# ESP32_with_USBC.net
KiCad netlist of a schematic drawn in Altium Designer
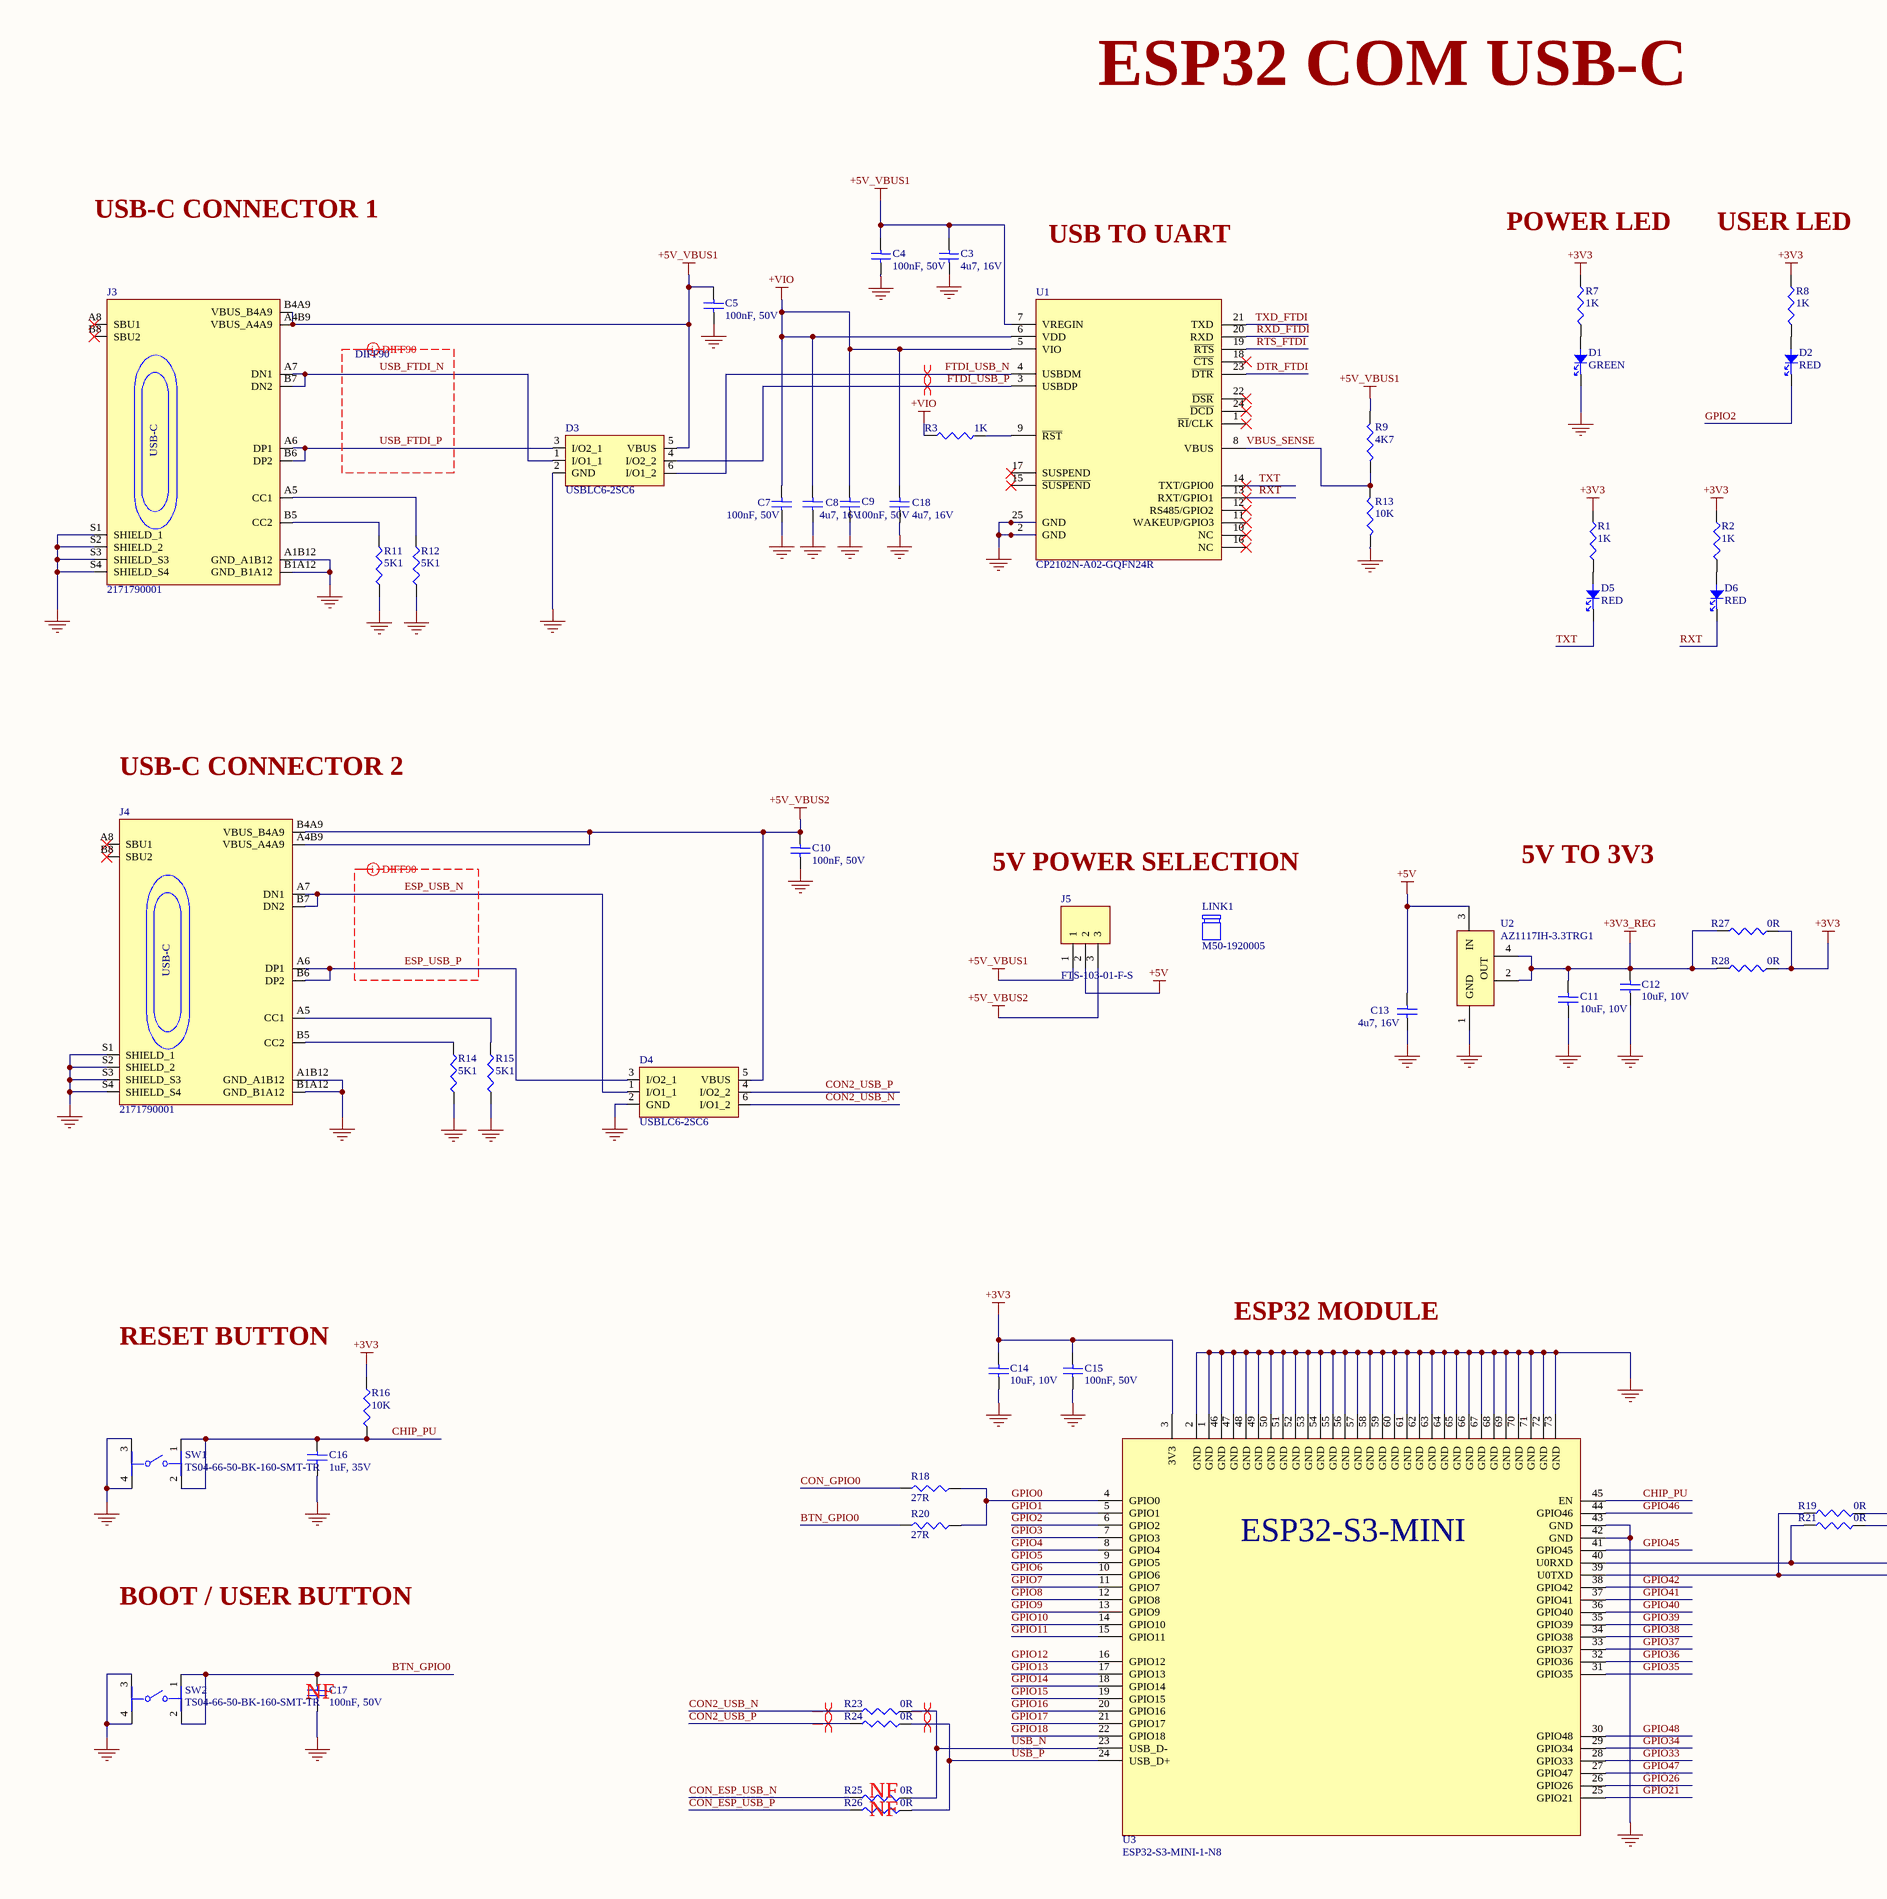
[diagram p0: ESP32 with USBC.SchDoc, left]
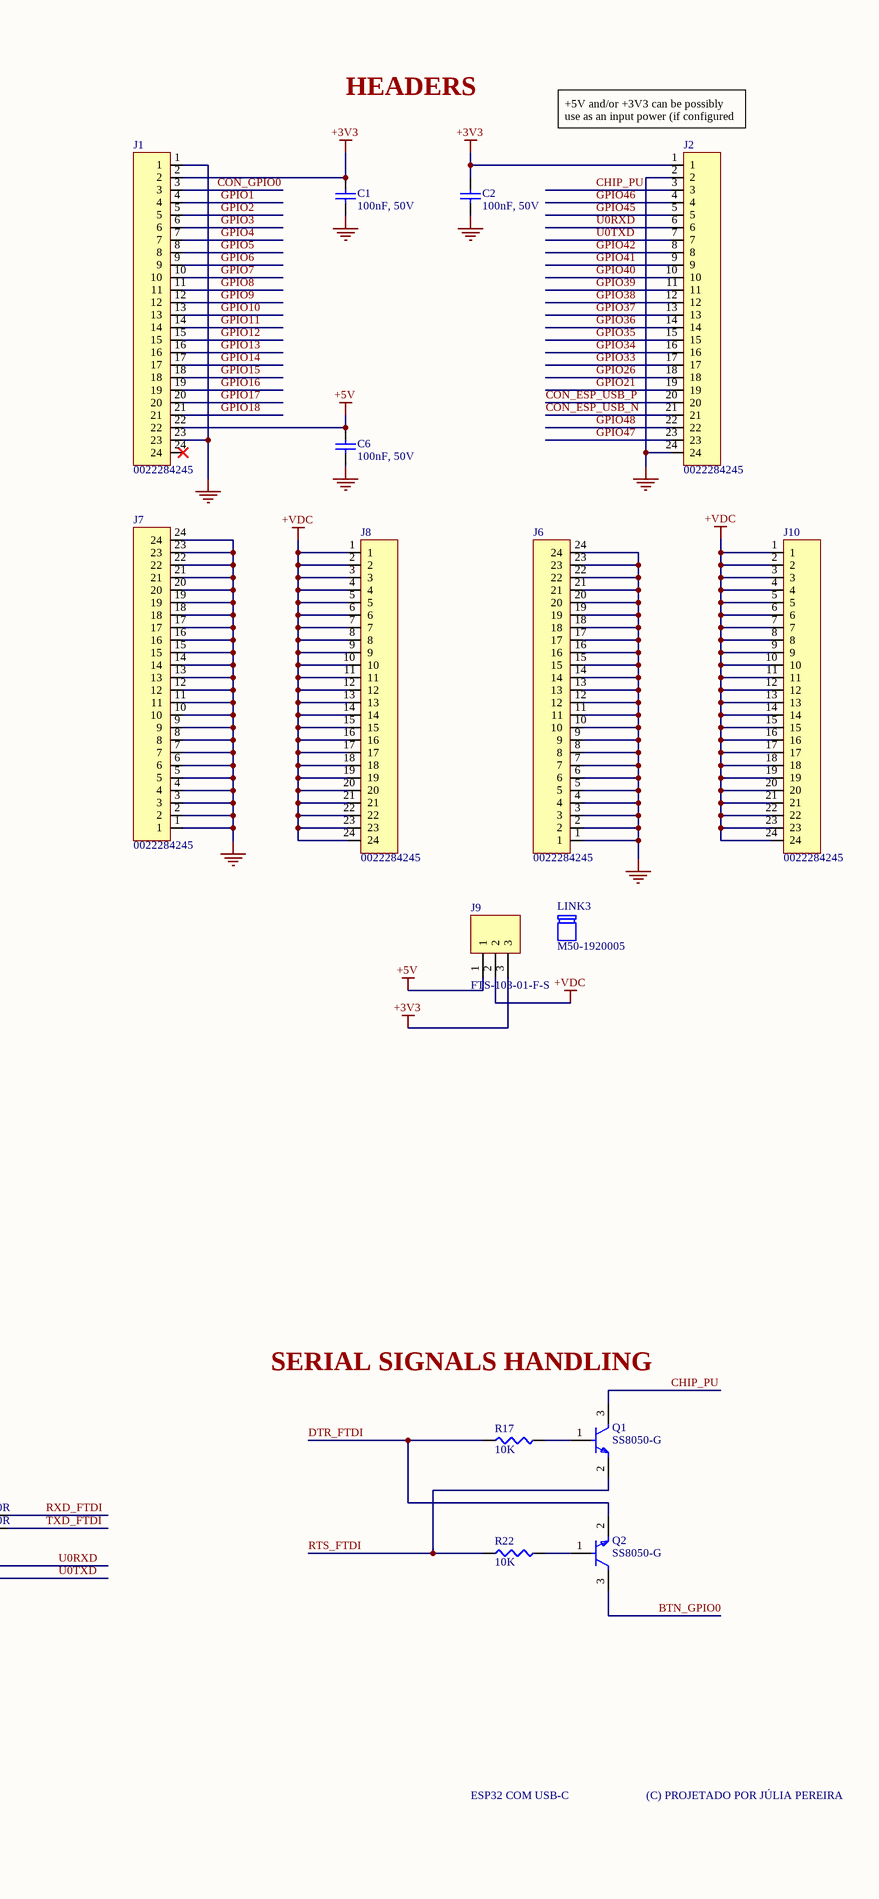
[diagram p1: ESP32 with USBC.SchDoc, right]

(export (version "E")
  (design (tool "Eeschema 10.0.6"))
  (components
    (comp (ref "C1")
      (value "100nF, 50V")
      (footprint "CAPC1005X65N")
      (description "CAP CER 0.1UF 50V X7R 0402")
      (fields
        (field (name "MANUFACTURER") "Samsung Electro-Mechanics")
        (field (name "MANUFACTURER PART NUMBER") "CL05B104KB54PNC")
      )
      (libsource (lib "Schlib") (part "CL05B104KB54PNC"))
    )
    (comp (ref "C2")
      (value "100nF, 50V")
      (footprint "CAPC1005X65N")
      (description "CAP CER 0.1UF 50V X7R 0402")
      (fields
        (field (name "MANUFACTURER") "Samsung Electro-Mechanics")
        (field (name "MANUFACTURER PART NUMBER") "CL05B104KB54PNC")
      )
      (libsource (lib "Schlib") (part "CL05B104KB54PNC"))
    )
    (comp (ref "C3")
      (value "4u7, 16V")
      (footprint "CAPC1005X65N")
      (description "4.7 µF ±20% 16V Capacitor de cerâmica X5R 0402 (métrico 1005)")
      (fields
        (field (name "MANUFACTURER") "Samsung Electro-Mechanics")
        (field (name "MANUFACTURER PART NUMBER") "CL05A475MO5NUNC")
      )
      (libsource (lib "Schlib") (part "CL05A475MO5NUNC"))
    )
    (comp (ref "C4")
      (value "100nF, 50V")
      (footprint "CAPC1005X65N")
      (description "CAP CER 0.1UF 50V X7R 0402")
      (fields
        (field (name "MANUFACTURER") "Samsung Electro-Mechanics")
        (field (name "MANUFACTURER PART NUMBER") "CL05B104KB54PNC")
      )
      (libsource (lib "Schlib") (part "CL05B104KB54PNC"))
    )
    (comp (ref "C5")
      (value "100nF, 50V")
      (footprint "CAPC1005X65N")
      (description "CAP CER 0.1UF 50V X7R 0402")
      (fields
        (field (name "MANUFACTURER") "Samsung Electro-Mechanics")
        (field (name "MANUFACTURER PART NUMBER") "CL05B104KB54PNC")
      )
      (libsource (lib "Schlib") (part "CL05B104KB54PNC"))
    )
    (comp (ref "C6")
      (value "100nF, 50V")
      (footprint "CAPC1005X65N")
      (description "CAP CER 0.1UF 50V X7R 0402")
      (fields
        (field (name "MANUFACTURER") "Samsung Electro-Mechanics")
        (field (name "MANUFACTURER PART NUMBER") "CL05B104KB54PNC")
      )
      (libsource (lib "Schlib") (part "CL05B104KB54PNC"))
    )
    (comp (ref "C7")
      (value "100nF, 50V")
      (footprint "CAPC1005X65N")
      (description "CAP CER 0.1UF 50V X7R 0402")
      (fields
        (field (name "MANUFACTURER") "Samsung Electro-Mechanics")
        (field (name "MANUFACTURER PART NUMBER") "CL05B104KB54PNC")
      )
      (libsource (lib "Schlib") (part "CL05B104KB54PNC"))
    )
    (comp (ref "C8")
      (value "4u7, 16V")
      (footprint "CAPC1005X65N")
      (description "4.7 µF ±20% 16V Capacitor de cerâmica X5R 0402 (métrico 1005)")
      (fields
        (field (name "MANUFACTURER") "Samsung Electro-Mechanics")
        (field (name "MANUFACTURER PART NUMBER") "CL05A475MO5NUNC")
      )
      (libsource (lib "Schlib") (part "CL05A475MO5NUNC"))
    )
    (comp (ref "C9")
      (value "100nF, 50V")
      (footprint "CAPC1005X65N")
      (description "CAP CER 0.1UF 50V X7R 0402")
      (fields
        (field (name "MANUFACTURER") "Samsung Electro-Mechanics")
        (field (name "MANUFACTURER PART NUMBER") "CL05B104KB54PNC")
      )
      (libsource (lib "Schlib") (part "CL05B104KB54PNC"))
    )
    (comp (ref "C10")
      (value "100nF, 50V")
      (footprint "CAPC1005X65N")
      (description "CAP CER 0.1UF 50V X7R 0402")
      (fields
        (field (name "MANUFACTURER") "Samsung Electro-Mechanics")
        (field (name "MANUFACTURER PART NUMBER") "CL05B104KB54PNC")
      )
      (libsource (lib "Schlib") (part "CL05B104KB54PNC"))
    )
    (comp (ref "C11")
      (value "10uF, 10V")
      (footprint "CAPC1005X65N")
      (description "10 µF ±20% 10V Capacitor de cerâmica X5R 0402 (métrico 1005)")
      (fields
        (field (name "MANUFACTURER") "Samsung Electro-Mechanics")
        (field (name "MANUFACTURER PART NUMBER") "CL05A106MP8NUB8")
      )
      (libsource (lib "Schlib") (part "CL05A106MP8NUB8"))
    )
    (comp (ref "C12")
      (value "10uF, 10V")
      (footprint "CAPC1005X65N")
      (description "10 µF ±20% 10V Capacitor de cerâmica X5R 0402 (métrico 1005)")
      (fields
        (field (name "MANUFACTURER") "Samsung Electro-Mechanics")
        (field (name "MANUFACTURER PART NUMBER") "CL05A106MP8NUB8")
      )
      (libsource (lib "Schlib") (part "CL05A106MP8NUB8"))
    )
    (comp (ref "C13")
      (value "4u7, 16V")
      (footprint "CAPC1005X65N")
      (description "4.7 µF ±20% 16V Capacitor de cerâmica X5R 0402 (métrico 1005)")
      (fields
        (field (name "MANUFACTURER") "Samsung Electro-Mechanics")
        (field (name "MANUFACTURER PART NUMBER") "CL05A475MO5NUNC")
      )
      (libsource (lib "Schlib") (part "CL05A475MO5NUNC"))
    )
    (comp (ref "C14")
      (value "10uF, 10V")
      (footprint "CAPC1005X65N")
      (description "10 µF ±20% 10V Capacitor de cerâmica X5R 0402 (métrico 1005)")
      (fields
        (field (name "MANUFACTURER") "Samsung Electro-Mechanics")
        (field (name "MANUFACTURER PART NUMBER") "CL05A106MP8NUB8")
      )
      (libsource (lib "Schlib") (part "CL05A106MP8NUB8"))
    )
    (comp (ref "C15")
      (value "100nF, 50V")
      (footprint "CAPC1005X65N")
      (description "CAP CER 0.1UF 50V X7R 0402")
      (fields
        (field (name "MANUFACTURER") "Samsung Electro-Mechanics")
        (field (name "MANUFACTURER PART NUMBER") "CL05B104KB54PNC")
      )
      (libsource (lib "Schlib") (part "CL05B104KB54PNC"))
    )
    (comp (ref "C16")
      (value "1uF, 35V")
      (footprint "CAPC1005X65N")
      (description "1 µF ±10% 35V Capacitor de cerâmica X5R 0402 (métrico 1005)")
      (fields
        (field (name "MANUFACTURER") "Samsung Electro-Mechanics")
        (field (name "MANUFACTURER PART NUMBER") "CL05A105KL5NRNC")
      )
      (libsource (lib "Schlib") (part "CL05A105KL5NRNC"))
    )
    (comp (ref "C17")
      (value "100nF, 50V")
      (footprint "CAPC1005X65N")
      (description "CAP CER 0.1UF 50V X7R 0402")
      (fields
        (field (name "MANUFACTURER") "Samsung Electro-Mechanics")
        (field (name "MANUFACTURER PART NUMBER") "CL05B104KB54PNC")
      )
      (libsource (lib "Schlib") (part "CL05B104KB54PNC"))
    )
    (comp (ref "C18")
      (value "4u7, 16V")
      (footprint "CAPC1005X65N")
      (description "4.7 µF ±20% 16V Capacitor de cerâmica X5R 0402 (métrico 1005)")
      (fields
        (field (name "MANUFACTURER") "Samsung Electro-Mechanics")
        (field (name "MANUFACTURER PART NUMBER") "CL05A475MO5NUNC")
      )
      (libsource (lib "Schlib") (part "CL05A475MO5NUNC"))
    )
    (comp (ref "D1")
      (value "GREEN")
      (footprint "LED0402G")
      (description "Verde 528nm Indicadores LED - Discreto 2,8V 0402 (métrico 1005)")
      (fields
        (field (name "MANUFACTURER") "Vishay")
        (field (name "MANUFACTURER PART NUMBER") "VLMTG1500-GS08")
      )
      (libsource (lib "Schlib") (part "VLMTG1500-GS08"))
    )
    (comp (ref "D2")
      (value "RED")
      (footprint "LED0402R")
      (description "LED Uni-Color Super Red 639nm 2-Pin Chip 0402(1006Metric) T/R")
      (fields
        (field (name "MANUFACTURER") "Vishay")
        (field (name "MANUFACTURER PART NUMBER") "VLMS1500-GS08")
      )
      (libsource (lib "Schlib") (part "VLMS1500-GS08"))
    )
    (comp (ref "D3")
      (value "USBLC6-2SC6")
      (footprint "SOT23-6L_STM-L")
      (description "STMicroelectronics Uni-Directional TVS Diode Array, 17V Vcl Max, SMD, SOT-23, 6V Vbr Min")
      (fields (field (name "MANUFACTURER") "STMicroelectronics"))
      (libsource (lib "Schlib") (part "USBLC6-2SC6"))
    )
    (comp (ref "D4")
      (value "USBLC6-2SC6")
      (footprint "SOT23-6L_STM-L")
      (description "STMicroelectronics Uni-Directional TVS Diode Array, 17V Vcl Max, SMD, SOT-23, 6V Vbr Min")
      (fields (field (name "MANUFACTURER") "STMicroelectronics"))
      (libsource (lib "Schlib") (part "USBLC6-2SC6"))
    )
    (comp (ref "D5")
      (value "RED")
      (footprint "LED0402R")
      (description "LED Uni-Color Super Red 639nm 2-Pin Chip 0402(1006Metric) T/R")
      (fields
        (field (name "MANUFACTURER") "Vishay")
        (field (name "MANUFACTURER PART NUMBER") "VLMS1500-GS08")
      )
      (libsource (lib "Schlib") (part "VLMS1500-GS08"))
    )
    (comp (ref "D6")
      (value "RED")
      (footprint "LED0402R")
      (description "LED Uni-Color Super Red 639nm 2-Pin Chip 0402(1006Metric) T/R")
      (fields
        (field (name "MANUFACTURER") "Vishay")
        (field (name "MANUFACTURER PART NUMBER") "VLMS1500-GS08")
      )
      (libsource (lib "Schlib") (part "VLMS1500-GS08"))
    )
    (comp (ref "J1")
      (value "0022284245")
      (footprint "HDR_1X24_2.54MM")
      (description "Conector barra de pinos Furo passante 24 position 0,100\" (2,54mm)")
      (fields (field (name "MANUFACTURER") "Molex") (field (name "MANUFACTURER PART NUMBER") "22-28-4245"))
      (libsource (lib "") (part "0022284245_2"))
    )
    (comp (ref "J2")
      (value "0022284245")
      (footprint "HDR_1X24_2.54MM")
      (description "Conector barra de pinos Furo passante 24 position 0,100\" (2,54mm)")
      (fields (field (name "MANUFACTURER") "Molex") (field (name "MANUFACTURER PART NUMBER") "22-28-4245"))
      (libsource (lib "") (part "0022284245_1"))
    )
    (comp (ref "J3")
      (value "2171790001")
      (footprint "FP-2171790001-MFG")
      (fields (field (name "MANUFACTURER") "Molex") (field (name "MANUFACTURER PART NUMBER") "217179-0001"))
      (libsource (lib "Schlib") (part "217179-0001"))
    )
    (comp (ref "J4")
      (value "2171790001")
      (footprint "FP-2171790001-MFG")
      (fields (field (name "MANUFACTURER") "Molex") (field (name "MANUFACTURER PART NUMBER") "217179-0001"))
      (libsource (lib "Schlib") (part "217179-0001"))
    )
    (comp (ref "J5")
      (value "FTS-103-01-F-S")
      (footprint "HDR_1X3_2X54MM")
      (description "Conector barra de pinos Furo passante 3 position 0,050\" (1,27mm)")
      (fields (field (name "MANUFACTURER") "Samtec"))
      (libsource (lib "Schlib") (part "FTS-103-01-F-S"))
    )
    (comp (ref "J6")
      (value "0022284245")
      (footprint "HDR_1X24_2.54MM")
      (description "Conector barra de pinos Furo passante 24 position 0,100\" (2,54mm)")
      (fields (field (name "MANUFACTURER") "Molex") (field (name "MANUFACTURER PART NUMBER") "22-28-4245"))
      (libsource (lib "Schlib") (part "0022284245"))
    )
    (comp (ref "J7")
      (value "0022284245")
      (footprint "HDR_1X24_2.54MM")
      (description "Conector barra de pinos Furo passante 24 position 0,100\" (2,54mm)")
      (fields (field (name "MANUFACTURER") "Molex") (field (name "MANUFACTURER PART NUMBER") "22-28-4245"))
      (libsource (lib "Schlib") (part "0022284245"))
    )
    (comp (ref "J8")
      (value "0022284245")
      (footprint "HDR_1X24_2.54MM")
      (description "Conector barra de pinos Furo passante 24 position 0,100\" (2,54mm)")
      (fields (field (name "MANUFACTURER") "Molex") (field (name "MANUFACTURER PART NUMBER") "22-28-4245"))
      (libsource (lib "") (part "0022284245_1"))
    )
    (comp (ref "J9")
      (value "FTS-103-01-F-S")
      (footprint "HDR_1X3_2X54MM")
      (description "Conector barra de pinos Furo passante 3 position 0,050\" (1,27mm)")
      (fields (field (name "MANUFACTURER") "Samtec"))
      (libsource (lib "Schlib") (part "FTS-103-01-F-S"))
    )
    (comp (ref "J10")
      (value "0022284245")
      (footprint "HDR_1X24_2.54MM")
      (description "Conector barra de pinos Furo passante 24 position 0,100\" (2,54mm)")
      (fields (field (name "MANUFACTURER") "Molex") (field (name "MANUFACTURER PART NUMBER") "22-28-4245"))
      (libsource (lib "") (part "0022284245_1"))
    )
    (comp (ref "LINK1")
      (value "M50-1920005")
      (description "2 (1 x 2) Conector Shunt com posi玢o Vermelho Topo fechado 0,050\" (1,27mm) Ouro")
      (fields (field (name "MANUFACTURER") "Harwin"))
      (libsource (lib "Schlib") (part "M50-1920005"))
    )
    (comp (ref "LINK3")
      (value "M50-1920005")
      (description "2 (1 x 2) Conector Shunt com posi玢o Vermelho Topo fechado 0,050\" (1,27mm) Ouro")
      (fields (field (name "MANUFACTURER") "Harwin"))
      (libsource (lib "Schlib") (part "M50-1920005"))
    )
    (comp (ref "Q1")
      (value "SS8050-G")
      (footprint "FP-SS8050-G-IPC_B")
      (description "Transístor bipolar (BJT) NPN 25 V 1.5 A 100MHz 300 mW Montagem em superfície SOT-23-3")
      (fields (field (name "MANUFACTURER") "Comchip"))
      (libsource (lib "Schlib") (part "SS8050-G"))
    )
    (comp (ref "Q2")
      (value "SS8050-G")
      (footprint "FP-SS8050-G-IPC_B")
      (description "Transístor bipolar (BJT) NPN 25 V 1.5 A 100MHz 300 mW Montagem em superfície SOT-23-3")
      (fields (field (name "MANUFACTURER") "Comchip"))
      (libsource (lib "Schlib") (part "SS8050-G"))
    )
    (comp (ref "R1")
      (value "1K")
      (footprint "RESC1005X37N")
      (description "1 kOhms ±1% 0,063W, 1/16W Resistor de chip 0402 (métrico 1005) Resistente à umidade Filme grosso")
      (fields
        (field (name "MANUFACTURER") "Yageo Group")
        (field (name "MANUFACTURER PART NUMBER") "RC0402FR-071KL")
      )
      (libsource (lib "Schlib") (part "RC0402FR-071KL"))
    )
    (comp (ref "R2")
      (value "1K")
      (footprint "RESC1005X37N")
      (description "1 kOhms ±1% 0,063W, 1/16W Resistor de chip 0402 (métrico 1005) Resistente à umidade Filme grosso")
      (fields
        (field (name "MANUFACTURER") "Yageo Group")
        (field (name "MANUFACTURER PART NUMBER") "RC0402FR-071KL")
      )
      (libsource (lib "Schlib") (part "RC0402FR-071KL"))
    )
    (comp (ref "R3")
      (value "1K")
      (footprint "RESC1005X37N")
      (description "1 kOhms ±1% 0,063W, 1/16W Resistor de chip 0402 (métrico 1005) Resistente à umidade Filme grosso")
      (fields
        (field (name "MANUFACTURER") "Yageo Group")
        (field (name "MANUFACTURER PART NUMBER") "RC0402FR-071KL")
      )
      (libsource (lib "Schlib") (part "RC0402FR-071KL"))
    )
    (comp (ref "R7")
      (value "1K")
      (footprint "RESC1005X37N")
      (description "1 kOhms ±1% 0,063W, 1/16W Resistor de chip 0402 (métrico 1005) Resistente à umidade Filme grosso")
      (fields
        (field (name "MANUFACTURER") "Yageo Group")
        (field (name "MANUFACTURER PART NUMBER") "RC0402FR-071KL")
      )
      (libsource (lib "Schlib") (part "RC0402FR-071KL"))
    )
    (comp (ref "R8")
      (value "1K")
      (footprint "RESC1005X37N")
      (description "1 kOhms ±1% 0,063W, 1/16W Resistor de chip 0402 (métrico 1005) Resistente à umidade Filme grosso")
      (fields
        (field (name "MANUFACTURER") "Yageo Group")
        (field (name "MANUFACTURER PART NUMBER") "RC0402FR-071KL")
      )
      (libsource (lib "Schlib") (part "RC0402FR-071KL"))
    )
    (comp (ref "R9")
      (value "4K7")
      (footprint "RESC1005X37N")
      (description "RES 4.7K OHM 1% 1/16W 0402")
      (fields
        (field (name "MANUFACTURER") "Yageo Group")
        (field (name "MANUFACTURER PART NUMBER") "RC0402FR-074K7L")
      )
      (libsource (lib "Schlib") (part "RC0402FR-074K7L"))
    )
    (comp (ref "R11")
      (value "5K1")
      (footprint "RESC1005X37N")
      (fields
        (field (name "MANUFACTURER") "Yageo Group")
        (field (name "MANUFACTURER PART NUMBER") "AC0402FR-075K1L")
        (field (name "TOLERANCE") "1%")
      )
      (libsource (lib "Schlib") (part "AC0402FR-075K1L"))
    )
    (comp (ref "R12")
      (value "5K1")
      (footprint "RESC1005X37N")
      (fields
        (field (name "MANUFACTURER") "Yageo Group")
        (field (name "MANUFACTURER PART NUMBER") "AC0402FR-075K1L")
        (field (name "TOLERANCE") "1%")
      )
      (libsource (lib "Schlib") (part "AC0402FR-075K1L"))
    )
    (comp (ref "R13")
      (value "10K")
      (footprint "RESC1005X37N")
      (fields
        (field (name "MANUFACTURER") "Yageo Group")
        (field (name "MANUFACTURER PART NUMBER") "AC0402FR-0710KL")
        (field (name "TOLERANCE") "1%")
      )
      (libsource (lib "Schlib") (part "AC0402FR-0710KL"))
    )
    (comp (ref "R14")
      (value "5K1")
      (footprint "RESC1005X37N")
      (fields
        (field (name "MANUFACTURER") "Yageo Group")
        (field (name "MANUFACTURER PART NUMBER") "AC0402FR-075K1L")
        (field (name "TOLERANCE") "1%")
      )
      (libsource (lib "Schlib") (part "AC0402FR-075K1L"))
    )
    (comp (ref "R15")
      (value "5K1")
      (footprint "RESC1005X37N")
      (fields
        (field (name "MANUFACTURER") "Yageo Group")
        (field (name "MANUFACTURER PART NUMBER") "AC0402FR-075K1L")
        (field (name "TOLERANCE") "1%")
      )
      (libsource (lib "Schlib") (part "AC0402FR-075K1L"))
    )
    (comp (ref "R16")
      (value "10K")
      (footprint "RESC1005X37N")
      (fields
        (field (name "MANUFACTURER") "Yageo Group")
        (field (name "MANUFACTURER PART NUMBER") "AC0402FR-0710KL")
        (field (name "TOLERANCE") "1%")
      )
      (libsource (lib "Schlib") (part "AC0402FR-0710KL"))
    )
    (comp (ref "R17")
      (value "10K")
      (footprint "RESC1005X37N")
      (fields
        (field (name "MANUFACTURER") "Yageo Group")
        (field (name "MANUFACTURER PART NUMBER") "AC0402FR-0710KL")
        (field (name "TOLERANCE") "1%")
      )
      (libsource (lib "Schlib") (part "AC0402FR-0710KL"))
    )
    (comp (ref "R18")
      (value "27R")
      (footprint "RESC1005X37N")
      (description "27 Ohms ±1% 0,063W, 1/16W Resistor de chip 0402 (métrico 1005) Resistente à umidade Filme grosso")
      (fields
        (field (name "MANUFACTURER") "Yageo Group")
        (field (name "MANUFACTURER PART NUMBER") "RC0402FR-0727RL")
      )
      (libsource (lib "Schlib") (part "RC0402FR-0727RL"))
    )
    (comp (ref "R19")
      (value "0R")
      (footprint "RESC1005X37N")
      (description "0 Ohms Jumper Resistor de chip 0402 (métrico 1005) Resistente à umidade Filme grosso")
      (fields
        (field (name "MANUFACTURER") "Yageo Group")
        (field (name "MANUFACTURER PART NUMBER") "RC0402JR-070RL")
      )
      (libsource (lib "Schlib") (part "RC0402JR-070RL"))
    )
    (comp (ref "R20")
      (value "27R")
      (footprint "RESC1005X37N")
      (description "27 Ohms ±1% 0,063W, 1/16W Resistor de chip 0402 (métrico 1005) Resistente à umidade Filme grosso")
      (fields
        (field (name "MANUFACTURER") "Yageo Group")
        (field (name "MANUFACTURER PART NUMBER") "RC0402FR-0727RL")
      )
      (libsource (lib "Schlib") (part "RC0402FR-0727RL"))
    )
    (comp (ref "R21")
      (value "0R")
      (footprint "RESC1005X37N")
      (description "0 Ohms Jumper Resistor de chip 0402 (métrico 1005) Resistente à umidade Filme grosso")
      (fields
        (field (name "MANUFACTURER") "Yageo Group")
        (field (name "MANUFACTURER PART NUMBER") "RC0402JR-070RL")
      )
      (libsource (lib "Schlib") (part "RC0402JR-070RL"))
    )
    (comp (ref "R22")
      (value "10K")
      (footprint "RESC1005X37N")
      (fields
        (field (name "MANUFACTURER") "Yageo Group")
        (field (name "MANUFACTURER PART NUMBER") "AC0402FR-0710KL")
        (field (name "TOLERANCE") "1%")
      )
      (libsource (lib "Schlib") (part "AC0402FR-0710KL"))
    )
    (comp (ref "R23")
      (value "0R")
      (footprint "RESC1005X37N")
      (description "0 Ohms Jumper Resistor de chip 0402 (métrico 1005) Resistente à umidade Filme grosso")
      (fields
        (field (name "MANUFACTURER") "Yageo Group")
        (field (name "MANUFACTURER PART NUMBER") "RC0402JR-070RL")
      )
      (libsource (lib "Schlib") (part "RC0402JR-070RL"))
    )
    (comp (ref "R24")
      (value "0R")
      (footprint "RESC1005X37N")
      (description "0 Ohms Jumper Resistor de chip 0402 (métrico 1005) Resistente à umidade Filme grosso")
      (fields
        (field (name "MANUFACTURER") "Yageo Group")
        (field (name "MANUFACTURER PART NUMBER") "RC0402JR-070RL")
      )
      (libsource (lib "Schlib") (part "RC0402JR-070RL"))
    )
    (comp (ref "R25")
      (value "0R")
      (footprint "RESC1005X37N")
      (description "0 Ohms Jumper Resistor de chip 0402 (métrico 1005) Resistente à umidade Filme grosso")
      (fields
        (field (name "MANUFACTURER") "Yageo Group")
        (field (name "MANUFACTURER PART NUMBER") "RC0402JR-070RL")
      )
      (libsource (lib "Schlib") (part "RC0402JR-070RL"))
    )
    (comp (ref "R26")
      (value "0R")
      (footprint "RESC1005X37N")
      (description "0 Ohms Jumper Resistor de chip 0402 (métrico 1005) Resistente à umidade Filme grosso")
      (fields
        (field (name "MANUFACTURER") "Yageo Group")
        (field (name "MANUFACTURER PART NUMBER") "RC0402JR-070RL")
      )
      (libsource (lib "Schlib") (part "RC0402JR-070RL"))
    )
    (comp (ref "R27")
      (value "0R")
      (footprint "RESC2012X60N")
      (description "RESA-AS 0805 0R JUMPER 125MW")
      (fields
        (field (name "MANUFACTURER") "Bourns")
        (field (name "MANUFACTURER PART NUMBER") "CR0805AJ/-000EAS")
      )
      (libsource (lib "Schlib") (part "CR0805AJ/-000EAS"))
    )
    (comp (ref "R28")
      (value "0R")
      (footprint "RESC2012X60N")
      (description "RESA-AS 0805 0R JUMPER 125MW")
      (fields
        (field (name "MANUFACTURER") "Bourns")
        (field (name "MANUFACTURER PART NUMBER") "CR0805AJ/-000EAS")
      )
      (libsource (lib "Schlib") (part "CR0805AJ/-000EAS"))
    )
    (comp (ref "SW1")
      (value "TS04-66-50-BK-160-SMT-TR")
      (footprint "TS04-66-50-BK-160-SMT-TR")
      (description "6 x 6 mm, 5 mm Actuator Height Off PCB, 160 gf, Black, Surface Mount, SPST, Tactile Switch")
      (fields (field (name "MANUFACTURER") "Same Sky"))
      (libsource (lib "Schlib") (part "TS04-66-50-BK-160-SMT-TR"))
    )
    (comp (ref "SW2")
      (value "TS04-66-50-BK-160-SMT-TR")
      (footprint "TS04-66-50-BK-160-SMT-TR")
      (description "6 x 6 mm, 5 mm Actuator Height Off PCB, 160 gf, Black, Surface Mount, SPST, Tactile Switch")
      (fields (field (name "MANUFACTURER") "Same Sky"))
      (libsource (lib "Schlib") (part "TS04-66-50-BK-160-SMT-TR"))
    )
    (comp (ref "U1")
      (value "CP2102N-A02-GQFN24R")
      (footprint "QFN50P400X400X80-25N")
      (description "IC Usb to Uart Bridge QFN24 / Usb Bridge, Usb to Uart Usb 2.0 Uart Interface 24-QFN (4X4)")
      (fields (field (name "MANUFACTURER") "Silicon Lab"))
      (libsource (lib "Schlib") (part "CP2102N-A02-GQFN24R"))
    )
    (comp (ref "U2")
      (value "AZ1117IH-3.3TRG1")
      (footprint "DCY0004A_N")
      (description "LDO Voltage Regulator, 1 Output, Fixed, 0-15V in, 3.3V Out, 1.2V Drop, 1A out, SOT-223-3")
      (fields (field (name "MANUFACTURER") "Diodes Inc."))
      (libsource (lib "Schlib") (part "AZ1117IH-3.3TRG1"))
    )
    (comp (ref "U3")
      (value "ESP32-S3-MINI-1-N8")
      (footprint "XCVR_ESP32-S3-MINI-1-N8")
      (description "20.5dBm ESP32-S3FN8 Chip 2.4GHz SMD WiFi Modules ROHS")
      (fields (field (name "MANUFACTURER") "Espressif Systems"))
      (libsource (lib "Schlib") (part "ESP32-S3-MINI-1-N8"))
    )
  )
  (nets
    (net (code "1") (name "+3V3") (class "Default")
      (node (ref "C1") (pin "2") (pinfunction "2_2") (pintype "passive"))
      (node (ref "C14") (pin "2") (pinfunction "2_2") (pintype "passive"))
      (node (ref "C15") (pin "2") (pinfunction "2_2") (pintype "passive"))
      (node (ref "C2") (pin "2") (pinfunction "2_2") (pintype "passive"))
      (node (ref "J1") (pin "2") (pinfunction "2_2") (pintype "passive"))
      (node (ref "J2") (pin "1") (pinfunction "1_1") (pintype "passive"))
      (node (ref "J9") (pin "3") (pinfunction "3_3") (pintype "passive"))
      (node (ref "R1") (pin "2") (pinfunction "2_2") (pintype "passive"))
      (node (ref "R16") (pin "2") (pinfunction "2_2") (pintype "passive"))
      (node (ref "R2") (pin "2") (pinfunction "2_2") (pintype "passive"))
      (node (ref "R27") (pin "2") (pinfunction "2_2") (pintype "passive"))
      (node (ref "R28") (pin "2") (pinfunction "2_2") (pintype "passive"))
      (node (ref "R7") (pin "2") (pinfunction "2_2") (pintype "passive"))
      (node (ref "R8") (pin "2") (pinfunction "2_2") (pintype "passive"))
      (node (ref "U3") (pin "3") (pinfunction "3V3_3") (pintype "passive"))
    )
    (net (code "2") (name "+3V3_REG") (class "Default")
      (node (ref "C11") (pin "2") (pinfunction "2_2") (pintype "passive"))
      (node (ref "C12") (pin "2") (pinfunction "2_2") (pintype "passive"))
      (node (ref "R27") (pin "1") (pinfunction "1_1") (pintype "passive"))
      (node (ref "R28") (pin "1") (pinfunction "1_1") (pintype "passive"))
      (node (ref "U2") (pin "2") (pinfunction "OUT_2") (pintype "power_in"))
      (node (ref "U2") (pin "4") (pinfunction "OUT_4") (pintype "power_in"))
    )
    (net (code "3") (name "+5V") (class "Default")
      (node (ref "C13") (pin "2") (pinfunction "2_2") (pintype "passive"))
      (node (ref "C6") (pin "2") (pinfunction "2_2") (pintype "passive"))
      (node (ref "J1") (pin "22") (pinfunction "22_22") (pintype "passive"))
      (node (ref "J5") (pin "2") (pinfunction "2_2") (pintype "passive"))
      (node (ref "J9") (pin "1") (pinfunction "1_1") (pintype "passive"))
      (node (ref "U2") (pin "3") (pinfunction "IN_3") (pintype "power_in"))
    )
    (net (code "4") (name "+5V_VBUS1") (class "Default")
      (node (ref "C3") (pin "2") (pinfunction "2_2") (pintype "passive"))
      (node (ref "C4") (pin "2") (pinfunction "2_2") (pintype "passive"))
      (node (ref "C5") (pin "2") (pinfunction "2_2") (pintype "passive"))
      (node (ref "D3") (pin "5") (pinfunction "VBUS_5") (pintype "passive"))
      (node (ref "J3") (pin "A4B9") (pinfunction "VBUS_A4A9_A4B9") (pintype "passive"))
      (node (ref "J3") (pin "B4A9") (pinfunction "VBUS_B4A9_B4A9") (pintype "passive"))
      (node (ref "J5") (pin "1") (pinfunction "1_1") (pintype "passive"))
      (node (ref "R9") (pin "2") (pinfunction "2_2") (pintype "passive"))
      (node (ref "U1") (pin "7") (pinfunction "VREGIN_7") (pintype "passive"))
    )
    (net (code "5") (name "+5V_VBUS2") (class "Default")
      (node (ref "C10") (pin "2") (pinfunction "2_2") (pintype "passive"))
      (node (ref "D4") (pin "5") (pinfunction "VBUS_5") (pintype "passive"))
      (node (ref "J4") (pin "A4B9") (pinfunction "VBUS_A4A9_A4B9") (pintype "passive"))
      (node (ref "J4") (pin "B4A9") (pinfunction "VBUS_B4A9_B4A9") (pintype "passive"))
      (node (ref "J5") (pin "3") (pinfunction "3_3") (pintype "passive"))
    )
    (net (code "6") (name "+VDC") (class "Default")
      (node (ref "J10") (pin "1") (pinfunction "1_1") (pintype "passive"))
      (node (ref "J10") (pin "10") (pinfunction "10_10") (pintype "passive"))
      (node (ref "J10") (pin "11") (pinfunction "11_11") (pintype "passive"))
      (node (ref "J10") (pin "12") (pinfunction "12_12") (pintype "passive"))
      (node (ref "J10") (pin "13") (pinfunction "13_13") (pintype "passive"))
      (node (ref "J10") (pin "14") (pinfunction "14_14") (pintype "passive"))
      (node (ref "J10") (pin "15") (pinfunction "15_15") (pintype "passive"))
      (node (ref "J10") (pin "16") (pinfunction "16_16") (pintype "passive"))
      (node (ref "J10") (pin "17") (pinfunction "17_17") (pintype "passive"))
      (node (ref "J10") (pin "18") (pinfunction "18_18") (pintype "passive"))
      (node (ref "J10") (pin "19") (pinfunction "19_19") (pintype "passive"))
      (node (ref "J10") (pin "2") (pinfunction "2_2") (pintype "passive"))
      (node (ref "J10") (pin "20") (pinfunction "20_20") (pintype "passive"))
      (node (ref "J10") (pin "21") (pinfunction "21_21") (pintype "passive"))
      (node (ref "J10") (pin "22") (pinfunction "22_22") (pintype "passive"))
      (node (ref "J10") (pin "23") (pinfunction "23_23") (pintype "passive"))
      (node (ref "J10") (pin "24") (pinfunction "24_24") (pintype "passive"))
      (node (ref "J10") (pin "3") (pinfunction "3_3") (pintype "passive"))
      (node (ref "J10") (pin "4") (pinfunction "4_4") (pintype "passive"))
      (node (ref "J10") (pin "5") (pinfunction "5_5") (pintype "passive"))
      (node (ref "J10") (pin "6") (pinfunction "6_6") (pintype "passive"))
      (node (ref "J10") (pin "7") (pinfunction "7_7") (pintype "passive"))
      (node (ref "J10") (pin "8") (pinfunction "8_8") (pintype "passive"))
      (node (ref "J10") (pin "9") (pinfunction "9_9") (pintype "passive"))
      (node (ref "J8") (pin "1") (pinfunction "1_1") (pintype "passive"))
      (node (ref "J8") (pin "10") (pinfunction "10_10") (pintype "passive"))
      (node (ref "J8") (pin "11") (pinfunction "11_11") (pintype "passive"))
      (node (ref "J8") (pin "12") (pinfunction "12_12") (pintype "passive"))
      (node (ref "J8") (pin "13") (pinfunction "13_13") (pintype "passive"))
      (node (ref "J8") (pin "14") (pinfunction "14_14") (pintype "passive"))
      (node (ref "J8") (pin "15") (pinfunction "15_15") (pintype "passive"))
      (node (ref "J8") (pin "16") (pinfunction "16_16") (pintype "passive"))
      (node (ref "J8") (pin "17") (pinfunction "17_17") (pintype "passive"))
      (node (ref "J8") (pin "18") (pinfunction "18_18") (pintype "passive"))
      (node (ref "J8") (pin "19") (pinfunction "19_19") (pintype "passive"))
      (node (ref "J8") (pin "2") (pinfunction "2_2") (pintype "passive"))
      (node (ref "J8") (pin "20") (pinfunction "20_20") (pintype "passive"))
      (node (ref "J8") (pin "21") (pinfunction "21_21") (pintype "passive"))
      (node (ref "J8") (pin "22") (pinfunction "22_22") (pintype "passive"))
      (node (ref "J8") (pin "23") (pinfunction "23_23") (pintype "passive"))
      (node (ref "J8") (pin "24") (pinfunction "24_24") (pintype "passive"))
      (node (ref "J8") (pin "3") (pinfunction "3_3") (pintype "passive"))
      (node (ref "J8") (pin "4") (pinfunction "4_4") (pintype "passive"))
      (node (ref "J8") (pin "5") (pinfunction "5_5") (pintype "passive"))
      (node (ref "J8") (pin "6") (pinfunction "6_6") (pintype "passive"))
      (node (ref "J8") (pin "7") (pinfunction "7_7") (pintype "passive"))
      (node (ref "J8") (pin "8") (pinfunction "8_8") (pintype "passive"))
      (node (ref "J8") (pin "9") (pinfunction "9_9") (pintype "passive"))
      (node (ref "J9") (pin "2") (pinfunction "2_2") (pintype "passive"))
    )
    (net (code "7") (name "+VIO") (class "Default")
      (node (ref "C18") (pin "2") (pinfunction "2_2") (pintype "passive"))
      (node (ref "C7") (pin "2") (pinfunction "2_2") (pintype "passive"))
      (node (ref "C8") (pin "2") (pinfunction "2_2") (pintype "passive"))
      (node (ref "C9") (pin "2") (pinfunction "2_2") (pintype "passive"))
      (node (ref "R3") (pin "2") (pinfunction "2_2") (pintype "passive"))
      (node (ref "U1") (pin "5") (pinfunction "VIO_5") (pintype "passive"))
      (node (ref "U1") (pin "6") (pinfunction "VDD_6") (pintype "passive"))
    )
    (net (code "8") (name "/BTN_GPIO0") (class "Default")
      (node (ref "C17") (pin "2") (pinfunction "2_2") (pintype "passive"))
      (node (ref "Q2") (pin "3") (pinfunction "C_3") (pintype "passive"))
      (node (ref "R20") (pin "1") (pinfunction "1_1") (pintype "passive"))
      (node (ref "SW2") (pin "1") (pinfunction "1_1") (pintype "passive"))
      (node (ref "SW2") (pin "2") (pinfunction "2_2") (pintype "passive"))
    )
    (net (code "9") (name "/CHIP_PU") (class "Default")
      (node (ref "C16") (pin "2") (pinfunction "2_2") (pintype "passive"))
      (node (ref "J2") (pin "3") (pinfunction "3_3") (pintype "passive"))
      (node (ref "Q1") (pin "3") (pinfunction "C_3") (pintype "passive"))
      (node (ref "R16") (pin "1") (pinfunction "1_1") (pintype "passive"))
      (node (ref "SW1") (pin "1") (pinfunction "1_1") (pintype "passive"))
      (node (ref "SW1") (pin "2") (pinfunction "2_2") (pintype "passive"))
      (node (ref "U3") (pin "45") (pinfunction "EN_45") (pintype "passive"))
    )
    (net (code "10") (name "/CON2_USB_N") (class "Default")
      (node (ref "D4") (pin "6") (pinfunction "I/O1_2_6") (pintype "passive"))
      (node (ref "R23") (pin "1") (pinfunction "1_1") (pintype "passive"))
    )
    (net (code "11") (name "/CON2_USB_P") (class "Default")
      (node (ref "D4") (pin "4") (pinfunction "I/O2_2_4") (pintype "passive"))
      (node (ref "R24") (pin "1") (pinfunction "1_1") (pintype "passive"))
    )
    (net (code "12") (name "/CON_ESP_USB_N") (class "Default")
      (node (ref "J2") (pin "21") (pinfunction "21_21") (pintype "passive"))
      (node (ref "R25") (pin "1") (pinfunction "1_1") (pintype "passive"))
    )
    (net (code "13") (name "/CON_ESP_USB_P") (class "Default")
      (node (ref "J2") (pin "20") (pinfunction "20_20") (pintype "passive"))
      (node (ref "R26") (pin "1") (pinfunction "1_1") (pintype "passive"))
    )
    (net (code "14") (name "/CON_GPIO0") (class "Default")
      (node (ref "J1") (pin "3") (pinfunction "3_3") (pintype "passive"))
      (node (ref "R18") (pin "1") (pinfunction "1_1") (pintype "passive"))
    )
    (net (code "15") (name "/DTR_FTDI") (class "Default")
      (node (ref "Q2") (pin "2") (pinfunction "E_2") (pintype "passive"))
      (node (ref "R17") (pin "2") (pinfunction "2_2") (pintype "passive"))
      (node (ref "U1") (pin "23") (pinfunction "~{DTR}_23") (pintype "passive"))
    )
    (net (code "16") (name "/ESP_USB_N") (class "Default")
      (node (ref "D4") (pin "1") (pinfunction "I/O1_1_1") (pintype "passive"))
      (node (ref "J4") (pin "A7") (pinfunction "DN1_A7") (pintype "passive"))
      (node (ref "J4") (pin "B7") (pinfunction "DN2_B7") (pintype "passive"))
    )
    (net (code "17") (name "/ESP_USB_P") (class "Default")
      (node (ref "D4") (pin "3") (pinfunction "I/O2_1_3") (pintype "passive"))
      (node (ref "J4") (pin "A6") (pinfunction "DP1_A6") (pintype "passive"))
      (node (ref "J4") (pin "B6") (pinfunction "DP2_B6") (pintype "passive"))
    )
    (net (code "18") (name "/FTDI_USB_N") (class "Default")
      (node (ref "D3") (pin "6") (pinfunction "I/O1_2_6") (pintype "passive"))
      (node (ref "U1") (pin "4") (pinfunction "USBDM_4") (pintype "passive"))
    )
    (net (code "19") (name "/FTDI_USB_P") (class "Default")
      (node (ref "D3") (pin "4") (pinfunction "I/O2_2_4") (pintype "passive"))
      (node (ref "U1") (pin "3") (pinfunction "USBDP_3") (pintype "passive"))
    )
    (net (code "20") (name "/GPIO0") (class "Default")
      (node (ref "R18") (pin "2") (pinfunction "2_2") (pintype "passive"))
      (node (ref "R20") (pin "2") (pinfunction "2_2") (pintype "passive"))
      (node (ref "U3") (pin "4") (pinfunction "GPIO0_4") (pintype "passive"))
    )
    (net (code "21") (name "/GPIO1") (class "Default")
      (node (ref "J1") (pin "4") (pinfunction "4_4") (pintype "passive"))
      (node (ref "U3") (pin "5") (pinfunction "GPIO1_5") (pintype "passive"))
    )
    (net (code "22") (name "/GPIO2") (class "Default")
      (node (ref "D2") (pin "1") (pinfunction "1_1") (pintype "passive"))
      (node (ref "J1") (pin "5") (pinfunction "5_5") (pintype "passive"))
      (node (ref "U3") (pin "6") (pinfunction "GPIO2_6") (pintype "passive"))
    )
    (net (code "23") (name "/GPIO3") (class "Default")
      (node (ref "J1") (pin "6") (pinfunction "6_6") (pintype "passive"))
      (node (ref "U3") (pin "7") (pinfunction "GPIO3_7") (pintype "passive"))
    )
    (net (code "24") (name "/GPIO4") (class "Default")
      (node (ref "J1") (pin "7") (pinfunction "7_7") (pintype "passive"))
      (node (ref "U3") (pin "8") (pinfunction "GPIO4_8") (pintype "passive"))
    )
    (net (code "25") (name "/GPIO5") (class "Default")
      (node (ref "J1") (pin "8") (pinfunction "8_8") (pintype "passive"))
      (node (ref "U3") (pin "9") (pinfunction "GPIO5_9") (pintype "passive"))
    )
    (net (code "26") (name "/GPIO6") (class "Default")
      (node (ref "J1") (pin "9") (pinfunction "9_9") (pintype "passive"))
      (node (ref "U3") (pin "10") (pinfunction "GPIO6_10") (pintype "passive"))
    )
    (net (code "27") (name "/GPIO7") (class "Default")
      (node (ref "J1") (pin "10") (pinfunction "10_10") (pintype "passive"))
      (node (ref "U3") (pin "11") (pinfunction "GPIO7_11") (pintype "passive"))
    )
    (net (code "28") (name "/GPIO8") (class "Default")
      (node (ref "J1") (pin "11") (pinfunction "11_11") (pintype "passive"))
      (node (ref "U3") (pin "12") (pinfunction "GPIO8_12") (pintype "passive"))
    )
    (net (code "29") (name "/GPIO9") (class "Default")
      (node (ref "J1") (pin "12") (pinfunction "12_12") (pintype "passive"))
      (node (ref "U3") (pin "13") (pinfunction "GPIO9_13") (pintype "passive"))
    )
    (net (code "30") (name "/GPIO10") (class "Default")
      (node (ref "J1") (pin "13") (pinfunction "13_13") (pintype "passive"))
      (node (ref "U3") (pin "14") (pinfunction "GPIO10_14") (pintype "passive"))
    )
    (net (code "31") (name "/GPIO11") (class "Default")
      (node (ref "J1") (pin "14") (pinfunction "14_14") (pintype "passive"))
      (node (ref "U3") (pin "15") (pinfunction "GPIO11_15") (pintype "passive"))
    )
    (net (code "32") (name "/GPIO12") (class "Default")
      (node (ref "J1") (pin "15") (pinfunction "15_15") (pintype "passive"))
      (node (ref "U3") (pin "16") (pinfunction "GPIO12_16") (pintype "passive"))
    )
    (net (code "33") (name "/GPIO13") (class "Default")
      (node (ref "J1") (pin "16") (pinfunction "16_16") (pintype "passive"))
      (node (ref "U3") (pin "17") (pinfunction "GPIO13_17") (pintype "passive"))
    )
    (net (code "34") (name "/GPIO14") (class "Default")
      (node (ref "J1") (pin "17") (pinfunction "17_17") (pintype "passive"))
      (node (ref "U3") (pin "18") (pinfunction "GPIO14_18") (pintype "passive"))
    )
    (net (code "35") (name "/GPIO15") (class "Default")
      (node (ref "J1") (pin "18") (pinfunction "18_18") (pintype "passive"))
      (node (ref "U3") (pin "19") (pinfunction "GPIO15_19") (pintype "passive"))
    )
    (net (code "36") (name "/GPIO16") (class "Default")
      (node (ref "J1") (pin "19") (pinfunction "19_19") (pintype "passive"))
      (node (ref "U3") (pin "20") (pinfunction "GPIO16_20") (pintype "passive"))
    )
    (net (code "37") (name "/GPIO17") (class "Default")
      (node (ref "J1") (pin "20") (pinfunction "20_20") (pintype "passive"))
      (node (ref "U3") (pin "21") (pinfunction "GPIO17_21") (pintype "passive"))
    )
    (net (code "38") (name "/GPIO18") (class "Default")
      (node (ref "J1") (pin "21") (pinfunction "21_21") (pintype "passive"))
      (node (ref "U3") (pin "22") (pinfunction "GPIO18_22") (pintype "passive"))
    )
    (net (code "39") (name "/GPIO21") (class "Default")
      (node (ref "J2") (pin "19") (pinfunction "19_19") (pintype "passive"))
      (node (ref "U3") (pin "25") (pinfunction "GPIO21_25") (pintype "passive"))
    )
    (net (code "40") (name "/GPIO26") (class "Default")
      (node (ref "J2") (pin "18") (pinfunction "18_18") (pintype "passive"))
      (node (ref "U3") (pin "26") (pinfunction "GPIO26_26") (pintype "passive"))
    )
    (net (code "41") (name "/GPIO33") (class "Default")
      (node (ref "J2") (pin "17") (pinfunction "17_17") (pintype "passive"))
      (node (ref "U3") (pin "28") (pinfunction "GPIO33_28") (pintype "passive"))
    )
    (net (code "42") (name "/GPIO34") (class "Default")
      (node (ref "J2") (pin "16") (pinfunction "16_16") (pintype "passive"))
      (node (ref "U3") (pin "29") (pinfunction "GPIO34_29") (pintype "passive"))
    )
    (net (code "43") (name "/GPIO35") (class "Default")
      (node (ref "J2") (pin "15") (pinfunction "15_15") (pintype "passive"))
      (node (ref "U3") (pin "31") (pinfunction "GPIO35_31") (pintype "passive"))
    )
    (net (code "44") (name "/GPIO36") (class "Default")
      (node (ref "J2") (pin "14") (pinfunction "14_14") (pintype "passive"))
      (node (ref "U3") (pin "32") (pinfunction "GPIO36_32") (pintype "passive"))
    )
    (net (code "45") (name "/GPIO37") (class "Default")
      (node (ref "J2") (pin "13") (pinfunction "13_13") (pintype "passive"))
      (node (ref "U3") (pin "33") (pinfunction "GPIO37_33") (pintype "passive"))
    )
    (net (code "46") (name "/GPIO38") (class "Default")
      (node (ref "J2") (pin "12") (pinfunction "12_12") (pintype "passive"))
      (node (ref "U3") (pin "34") (pinfunction "GPIO38_34") (pintype "passive"))
    )
    (net (code "47") (name "/GPIO39") (class "Default")
      (node (ref "J2") (pin "11") (pinfunction "11_11") (pintype "passive"))
      (node (ref "U3") (pin "35") (pinfunction "GPIO39_35") (pintype "passive"))
    )
    (net (code "48") (name "/GPIO40") (class "Default")
      (node (ref "J2") (pin "10") (pinfunction "10_10") (pintype "passive"))
      (node (ref "U3") (pin "36") (pinfunction "GPIO40_36") (pintype "passive"))
    )
    (net (code "49") (name "/GPIO41") (class "Default")
      (node (ref "J2") (pin "9") (pinfunction "9_9") (pintype "passive"))
      (node (ref "U3") (pin "37") (pinfunction "GPIO41_37") (pintype "passive"))
    )
    (net (code "50") (name "/GPIO42") (class "Default")
      (node (ref "J2") (pin "8") (pinfunction "8_8") (pintype "passive"))
      (node (ref "U3") (pin "38") (pinfunction "GPIO42_38") (pintype "passive"))
    )
    (net (code "51") (name "/GPIO45") (class "Default")
      (node (ref "J2") (pin "5") (pinfunction "5_5") (pintype "passive"))
      (node (ref "U3") (pin "41") (pinfunction "GPIO45_41") (pintype "passive"))
    )
    (net (code "52") (name "/GPIO46") (class "Default")
      (node (ref "J2") (pin "4") (pinfunction "4_4") (pintype "passive"))
      (node (ref "U3") (pin "44") (pinfunction "GPIO46_44") (pintype "passive"))
    )
    (net (code "53") (name "/GPIO47") (class "Default")
      (node (ref "J2") (pin "23") (pinfunction "23_23") (pintype "passive"))
      (node (ref "U3") (pin "27") (pinfunction "GPIO47_27") (pintype "passive"))
    )
    (net (code "54") (name "/GPIO48") (class "Default")
      (node (ref "J2") (pin "22") (pinfunction "22_22") (pintype "passive"))
      (node (ref "U3") (pin "30") (pinfunction "GPIO48_30") (pintype "passive"))
    )
    (net (code "55") (name "/RTS_FTDI") (class "Default")
      (node (ref "Q1") (pin "2") (pinfunction "E_2") (pintype "passive"))
      (node (ref "R22") (pin "2") (pinfunction "2_2") (pintype "passive"))
      (node (ref "U1") (pin "19") (pinfunction "~{RTS}_19") (pintype "passive"))
    )
    (net (code "56") (name "/RXD_FTDI") (class "Default")
      (node (ref "R19") (pin "2") (pinfunction "2_2") (pintype "passive"))
      (node (ref "U1") (pin "20") (pinfunction "RXD_20") (pintype "passive"))
    )
    (net (code "57") (name "/RXT") (class "Default")
      (node (ref "D6") (pin "1") (pinfunction "1_1") (pintype "passive"))
      (node (ref "U1") (pin "13") (pinfunction "RXT/GPIO1_13") (pintype "passive"))
    )
    (net (code "58") (name "/TXD_FTDI") (class "Default")
      (node (ref "R21") (pin "2") (pinfunction "2_2") (pintype "passive"))
      (node (ref "U1") (pin "21") (pinfunction "TXD_21") (pintype "passive"))
    )
    (net (code "59") (name "/TXT") (class "Default")
      (node (ref "D5") (pin "1") (pinfunction "1_1") (pintype "passive"))
      (node (ref "U1") (pin "14") (pinfunction "TXT/GPIO0_14") (pintype "passive"))
    )
    (net (code "60") (name "/U0RXD") (class "Default")
      (node (ref "J2") (pin "6") (pinfunction "6_6") (pintype "passive"))
      (node (ref "R21") (pin "1") (pinfunction "1_1") (pintype "passive"))
      (node (ref "U3") (pin "40") (pinfunction "U0RXD_40") (pintype "passive"))
    )
    (net (code "61") (name "/U0TXD") (class "Default")
      (node (ref "J2") (pin "7") (pinfunction "7_7") (pintype "passive"))
      (node (ref "R19") (pin "1") (pinfunction "1_1") (pintype "passive"))
      (node (ref "U3") (pin "39") (pinfunction "U0TXD_39") (pintype "passive"))
    )
    (net (code "62") (name "/USB_FTDI_N") (class "Default")
      (node (ref "D3") (pin "1") (pinfunction "I/O1_1_1") (pintype "passive"))
      (node (ref "J3") (pin "A7") (pinfunction "DN1_A7") (pintype "passive"))
      (node (ref "J3") (pin "B7") (pinfunction "DN2_B7") (pintype "passive"))
    )
    (net (code "63") (name "/USB_FTDI_P") (class "Default")
      (node (ref "D3") (pin "3") (pinfunction "I/O2_1_3") (pintype "passive"))
      (node (ref "J3") (pin "A6") (pinfunction "DP1_A6") (pintype "passive"))
      (node (ref "J3") (pin "B6") (pinfunction "DP2_B6") (pintype "passive"))
    )
    (net (code "64") (name "/USB_N") (class "Default")
      (node (ref "R23") (pin "2") (pinfunction "2_2") (pintype "passive"))
      (node (ref "R25") (pin "2") (pinfunction "2_2") (pintype "passive"))
      (node (ref "U3") (pin "23") (pinfunction "USB_D-_23") (pintype "passive"))
    )
    (net (code "65") (name "/USB_P") (class "Default")
      (node (ref "R24") (pin "2") (pinfunction "2_2") (pintype "passive"))
      (node (ref "R26") (pin "2") (pinfunction "2_2") (pintype "passive"))
      (node (ref "U3") (pin "24") (pinfunction "USB_D+_24") (pintype "passive"))
    )
    (net (code "66") (name "/VBUS_SENSE") (class "Default")
      (node (ref "R13") (pin "2") (pinfunction "2_2") (pintype "passive"))
      (node (ref "R9") (pin "1") (pinfunction "1_1") (pintype "passive"))
      (node (ref "U1") (pin "8") (pinfunction "VBUS_8") (pintype "passive"))
    )
    (net (code "67") (name "GND") (class "Default")
      (node (ref "C1") (pin "1") (pinfunction "1_1") (pintype "passive"))
      (node (ref "C10") (pin "1") (pinfunction "1_1") (pintype "passive"))
      (node (ref "C11") (pin "1") (pinfunction "1_1") (pintype "passive"))
      (node (ref "C12") (pin "1") (pinfunction "1_1") (pintype "passive"))
      (node (ref "C13") (pin "1") (pinfunction "1_1") (pintype "passive"))
      (node (ref "C14") (pin "1") (pinfunction "1_1") (pintype "passive"))
      (node (ref "C15") (pin "1") (pinfunction "1_1") (pintype "passive"))
      (node (ref "C16") (pin "1") (pinfunction "1_1") (pintype "passive"))
      (node (ref "C17") (pin "1") (pinfunction "1_1") (pintype "passive"))
      (node (ref "C18") (pin "1") (pinfunction "1_1") (pintype "passive"))
      (node (ref "C2") (pin "1") (pinfunction "1_1") (pintype "passive"))
      (node (ref "C3") (pin "1") (pinfunction "1_1") (pintype "passive"))
      (node (ref "C4") (pin "1") (pinfunction "1_1") (pintype "passive"))
      (node (ref "C5") (pin "1") (pinfunction "1_1") (pintype "passive"))
      (node (ref "C6") (pin "1") (pinfunction "1_1") (pintype "passive"))
      (node (ref "C7") (pin "1") (pinfunction "1_1") (pintype "passive"))
      (node (ref "C8") (pin "1") (pinfunction "1_1") (pintype "passive"))
      (node (ref "C9") (pin "1") (pinfunction "1_1") (pintype "passive"))
      (node (ref "D1") (pin "1") (pinfunction "1_1") (pintype "passive"))
      (node (ref "D3") (pin "2") (pinfunction "GND_2") (pintype "passive"))
      (node (ref "D4") (pin "2") (pinfunction "GND_2") (pintype "passive"))
      (node (ref "J1") (pin "1") (pinfunction "1_1") (pintype "passive"))
      (node (ref "J1") (pin "23") (pinfunction "23_23") (pintype "passive"))
      (node (ref "J2") (pin "2") (pinfunction "2_2") (pintype "passive"))
      (node (ref "J2") (pin "24") (pinfunction "24_24") (pintype "passive"))
      (node (ref "J3") (pin "A1B12") (pinfunction "GND_A1B12_A1B12") (pintype "passive"))
      (node (ref "J3") (pin "B1A12") (pinfunction "GND_B1A12_B1A12") (pintype "passive"))
      (node (ref "J3") (pin "S1") (pinfunction "SHIELD_1_S1") (pintype "passive"))
      (node (ref "J3") (pin "S2") (pinfunction "SHIELD_2_S2") (pintype "passive"))
      (node (ref "J3") (pin "S3") (pinfunction "SHIELD_S3_S3") (pintype "passive"))
      (node (ref "J3") (pin "S4") (pinfunction "SHIELD_S4_S4") (pintype "passive"))
      (node (ref "J4") (pin "A1B12") (pinfunction "GND_A1B12_A1B12") (pintype "passive"))
      (node (ref "J4") (pin "B1A12") (pinfunction "GND_B1A12_B1A12") (pintype "passive"))
      (node (ref "J4") (pin "S1") (pinfunction "SHIELD_1_S1") (pintype "passive"))
      (node (ref "J4") (pin "S2") (pinfunction "SHIELD_2_S2") (pintype "passive"))
      (node (ref "J4") (pin "S3") (pinfunction "SHIELD_S3_S3") (pintype "passive"))
      (node (ref "J4") (pin "S4") (pinfunction "SHIELD_S4_S4") (pintype "passive"))
      (node (ref "J6") (pin "1") (pinfunction "1_1") (pintype "passive"))
      (node (ref "J6") (pin "10") (pinfunction "10_10") (pintype "passive"))
      (node (ref "J6") (pin "11") (pinfunction "11_11") (pintype "passive"))
      (node (ref "J6") (pin "12") (pinfunction "12_12") (pintype "passive"))
      (node (ref "J6") (pin "13") (pinfunction "13_13") (pintype "passive"))
      (node (ref "J6") (pin "14") (pinfunction "14_14") (pintype "passive"))
      (node (ref "J6") (pin "15") (pinfunction "15_15") (pintype "passive"))
      (node (ref "J6") (pin "16") (pinfunction "16_16") (pintype "passive"))
      (node (ref "J6") (pin "17") (pinfunction "17_17") (pintype "passive"))
      (node (ref "J6") (pin "18") (pinfunction "18_18") (pintype "passive"))
      (node (ref "J6") (pin "19") (pinfunction "19_19") (pintype "passive"))
      (node (ref "J6") (pin "2") (pinfunction "2_2") (pintype "passive"))
      (node (ref "J6") (pin "20") (pinfunction "20_20") (pintype "passive"))
      (node (ref "J6") (pin "21") (pinfunction "21_21") (pintype "passive"))
      (node (ref "J6") (pin "22") (pinfunction "22_22") (pintype "passive"))
      (node (ref "J6") (pin "23") (pinfunction "23_23") (pintype "passive"))
      (node (ref "J6") (pin "24") (pinfunction "24_24") (pintype "passive"))
      (node (ref "J6") (pin "3") (pinfunction "3_3") (pintype "passive"))
      (node (ref "J6") (pin "4") (pinfunction "4_4") (pintype "passive"))
      (node (ref "J6") (pin "5") (pinfunction "5_5") (pintype "passive"))
      (node (ref "J6") (pin "6") (pinfunction "6_6") (pintype "passive"))
      (node (ref "J6") (pin "7") (pinfunction "7_7") (pintype "passive"))
      (node (ref "J6") (pin "8") (pinfunction "8_8") (pintype "passive"))
      (node (ref "J6") (pin "9") (pinfunction "9_9") (pintype "passive"))
      (node (ref "J7") (pin "1") (pinfunction "1_1") (pintype "passive"))
      (node (ref "J7") (pin "10") (pinfunction "10_10") (pintype "passive"))
      (node (ref "J7") (pin "11") (pinfunction "11_11") (pintype "passive"))
      (node (ref "J7") (pin "12") (pinfunction "12_12") (pintype "passive"))
      (node (ref "J7") (pin "13") (pinfunction "13_13") (pintype "passive"))
      (node (ref "J7") (pin "14") (pinfunction "14_14") (pintype "passive"))
      (node (ref "J7") (pin "15") (pinfunction "15_15") (pintype "passive"))
      (node (ref "J7") (pin "16") (pinfunction "16_16") (pintype "passive"))
      (node (ref "J7") (pin "17") (pinfunction "17_17") (pintype "passive"))
      (node (ref "J7") (pin "18") (pinfunction "18_18") (pintype "passive"))
      (node (ref "J7") (pin "19") (pinfunction "19_19") (pintype "passive"))
      (node (ref "J7") (pin "2") (pinfunction "2_2") (pintype "passive"))
      (node (ref "J7") (pin "20") (pinfunction "20_20") (pintype "passive"))
      (node (ref "J7") (pin "21") (pinfunction "21_21") (pintype "passive"))
      (node (ref "J7") (pin "22") (pinfunction "22_22") (pintype "passive"))
      (node (ref "J7") (pin "23") (pinfunction "23_23") (pintype "passive"))
      (node (ref "J7") (pin "24") (pinfunction "24_24") (pintype "passive"))
      (node (ref "J7") (pin "3") (pinfunction "3_3") (pintype "passive"))
      (node (ref "J7") (pin "4") (pinfunction "4_4") (pintype "passive"))
      (node (ref "J7") (pin "5") (pinfunction "5_5") (pintype "passive"))
      (node (ref "J7") (pin "6") (pinfunction "6_6") (pintype "passive"))
      (node (ref "J7") (pin "7") (pinfunction "7_7") (pintype "passive"))
      (node (ref "J7") (pin "8") (pinfunction "8_8") (pintype "passive"))
      (node (ref "J7") (pin "9") (pinfunction "9_9") (pintype "passive"))
      (node (ref "R11") (pin "1") (pinfunction "1_1") (pintype "passive"))
      (node (ref "R12") (pin "1") (pinfunction "1_1") (pintype "passive"))
      (node (ref "R13") (pin "1") (pinfunction "1_1") (pintype "passive"))
      (node (ref "R14") (pin "1") (pinfunction "1_1") (pintype "passive"))
      (node (ref "R15") (pin "1") (pinfunction "1_1") (pintype "passive"))
      (node (ref "SW1") (pin "3") (pinfunction "3_3") (pintype "passive"))
      (node (ref "SW1") (pin "4") (pinfunction "4_4") (pintype "passive"))
      (node (ref "SW2") (pin "3") (pinfunction "3_3") (pintype "passive"))
      (node (ref "SW2") (pin "4") (pinfunction "4_4") (pintype "passive"))
      (node (ref "U1") (pin "2") (pinfunction "GND_2") (pintype "passive"))
      (node (ref "U1") (pin "25") (pinfunction "GND_25") (pintype "passive"))
      (node (ref "U2") (pin "1") (pinfunction "GND_1") (pintype "power_in"))
      (node (ref "U3") (pin "1") (pinfunction "GND_1") (pintype "passive"))
      (node (ref "U3") (pin "2") (pinfunction "GND_2") (pintype "passive"))
      (node (ref "U3") (pin "42") (pinfunction "GND_42") (pintype "passive"))
      (node (ref "U3") (pin "43") (pinfunction "GND_43") (pintype "passive"))
      (node (ref "U3") (pin "46") (pinfunction "GND_46") (pintype "passive"))
      (node (ref "U3") (pin "47") (pinfunction "GND_47") (pintype "passive"))
      (node (ref "U3") (pin "48") (pinfunction "GND_48") (pintype "passive"))
      (node (ref "U3") (pin "49") (pinfunction "GND_49") (pintype "passive"))
      (node (ref "U3") (pin "50") (pinfunction "GND_50") (pintype "passive"))
      (node (ref "U3") (pin "51") (pinfunction "GND_51") (pintype "passive"))
      (node (ref "U3") (pin "52") (pinfunction "GND_52") (pintype "passive"))
      (node (ref "U3") (pin "53") (pinfunction "GND_53") (pintype "passive"))
      (node (ref "U3") (pin "54") (pinfunction "GND_54") (pintype "passive"))
      (node (ref "U3") (pin "55") (pinfunction "GND_55") (pintype "passive"))
      (node (ref "U3") (pin "56") (pinfunction "GND_56") (pintype "passive"))
      (node (ref "U3") (pin "57") (pinfunction "GND_57") (pintype "passive"))
      (node (ref "U3") (pin "58") (pinfunction "GND_58") (pintype "passive"))
      (node (ref "U3") (pin "59") (pinfunction "GND_59") (pintype "passive"))
      (node (ref "U3") (pin "60") (pinfunction "GND_60") (pintype "passive"))
      (node (ref "U3") (pin "61") (pinfunction "GND_61") (pintype "passive"))
      (node (ref "U3") (pin "62") (pinfunction "GND_62") (pintype "passive"))
      (node (ref "U3") (pin "63") (pinfunction "GND_63") (pintype "passive"))
      (node (ref "U3") (pin "64") (pinfunction "GND_64") (pintype "passive"))
      (node (ref "U3") (pin "65") (pinfunction "GND_65") (pintype "passive"))
      (node (ref "U3") (pin "66") (pinfunction "GND_66") (pintype "passive"))
      (node (ref "U3") (pin "67") (pinfunction "GND_67") (pintype "passive"))
      (node (ref "U3") (pin "68") (pinfunction "GND_68") (pintype "passive"))
      (node (ref "U3") (pin "69") (pinfunction "GND_69") (pintype "passive"))
      (node (ref "U3") (pin "70") (pinfunction "GND_70") (pintype "passive"))
      (node (ref "U3") (pin "71") (pinfunction "GND_71") (pintype "passive"))
      (node (ref "U3") (pin "72") (pinfunction "GND_72") (pintype "passive"))
      (node (ref "U3") (pin "73") (pinfunction "GND_73") (pintype "passive"))
    )
    (net (code "68") (name "Net-(D1-Pad2)") (class "Default")
      (node (ref "D1") (pin "2") (pinfunction "2_2") (pintype "passive"))
      (node (ref "R7") (pin "1") (pinfunction "1_1") (pintype "passive"))
    )
    (net (code "69") (name "Net-(D2-Pad2)") (class "Default")
      (node (ref "D2") (pin "2") (pinfunction "2_2") (pintype "passive"))
      (node (ref "R8") (pin "1") (pinfunction "1_1") (pintype "passive"))
    )
    (net (code "70") (name "Net-(D5-Pad2)") (class "Default")
      (node (ref "D5") (pin "2") (pinfunction "2_2") (pintype "passive"))
      (node (ref "R1") (pin "1") (pinfunction "1_1") (pintype "passive"))
    )
    (net (code "71") (name "Net-(D6-Pad2)") (class "Default")
      (node (ref "D6") (pin "2") (pinfunction "2_2") (pintype "passive"))
      (node (ref "R2") (pin "1") (pinfunction "1_1") (pintype "passive"))
    )
    (net (code "72") (name "Net-(J3-CC1)") (class "Default")
      (node (ref "J3") (pin "A5") (pinfunction "CC1_A5") (pintype "passive"))
      (node (ref "R12") (pin "2") (pinfunction "2_2") (pintype "passive"))
    )
    (net (code "73") (name "Net-(J3-CC2)") (class "Default")
      (node (ref "J3") (pin "B5") (pinfunction "CC2_B5") (pintype "passive"))
      (node (ref "R11") (pin "2") (pinfunction "2_2") (pintype "passive"))
    )
    (net (code "74") (name "Net-(J4-CC1)") (class "Default")
      (node (ref "J4") (pin "A5") (pinfunction "CC1_A5") (pintype "passive"))
      (node (ref "R15") (pin "2") (pinfunction "2_2") (pintype "passive"))
    )
    (net (code "75") (name "Net-(J4-CC2)") (class "Default")
      (node (ref "J4") (pin "B5") (pinfunction "CC2_B5") (pintype "passive"))
      (node (ref "R14") (pin "2") (pinfunction "2_2") (pintype "passive"))
    )
    (net (code "76") (name "Net-(Q1-B)") (class "Default")
      (node (ref "Q1") (pin "1") (pinfunction "B_1") (pintype "passive"))
      (node (ref "R17") (pin "1") (pinfunction "1_1") (pintype "passive"))
    )
    (net (code "77") (name "Net-(Q2-B)") (class "Default")
      (node (ref "Q2") (pin "1") (pinfunction "B_1") (pintype "passive"))
      (node (ref "R22") (pin "1") (pinfunction "1_1") (pintype "passive"))
    )
    (net (code "78") (name "Net-(U1-~{RST})") (class "Default")
      (node (ref "R3") (pin "1") (pinfunction "1_1") (pintype "passive"))
      (node (ref "U1") (pin "9") (pinfunction "~{RST}_9") (pintype "passive"))
    )
    (net (code "79") (name "unconnected-(J1-Pad24)") (class "Default")
      (node (ref "J1") (pin "24") (pinfunction "24_24") (pintype "passive+no_connect"))
    )
    (net (code "80") (name "unconnected-(J3-SBU1-PadA8)") (class "Default")
      (node (ref "J3") (pin "A8") (pinfunction "SBU1_A8") (pintype "passive+no_connect"))
    )
    (net (code "81") (name "unconnected-(J3-SBU2-PadB8)") (class "Default")
      (node (ref "J3") (pin "B8") (pinfunction "SBU2_B8") (pintype "passive+no_connect"))
    )
    (net (code "82") (name "unconnected-(J4-SBU1-PadA8)") (class "Default")
      (node (ref "J4") (pin "A8") (pinfunction "SBU1_A8") (pintype "passive+no_connect"))
    )
    (net (code "83") (name "unconnected-(J4-SBU2-PadB8)") (class "Default")
      (node (ref "J4") (pin "B8") (pinfunction "SBU2_B8") (pintype "passive+no_connect"))
    )
    (net (code "84") (name "unconnected-(U1-NC-Pad10)") (class "Default")
      (node (ref "U1") (pin "10") (pinfunction "NC_10") (pintype "passive+no_connect"))
    )
    (net (code "85") (name "unconnected-(U1-NC-Pad16)") (class "Default")
      (node (ref "U1") (pin "16") (pinfunction "NC_16") (pintype "passive+no_connect"))
    )
    (net (code "86") (name "unconnected-(U1-RS485{slash}GPIO2-Pad12)") (class "Default")
      (node (ref "U1") (pin "12") (pinfunction "RS485/GPIO2_12") (pintype "passive+no_connect"))
    )
    (net (code "87") (name "unconnected-(U1-SUSPEND-Pad17)") (class "Default")
      (node (ref "U1") (pin "17") (pinfunction "SUSPEND_17") (pintype "passive+no_connect"))
    )
    (net (code "88") (name "unconnected-(U1-WAKEUP{slash}GPIO3-Pad11)") (class "Default")
      (node (ref "U1") (pin "11") (pinfunction "WAKEUP/GPIO3_11") (pintype "passive+no_connect"))
    )
    (net (code "89") (name "unconnected-(U1-~{CTS}-Pad18)") (class "Default")
      (node (ref "U1") (pin "18") (pinfunction "~{CTS}_18") (pintype "passive+no_connect"))
    )
    (net (code "90") (name "unconnected-(U1-~{DCD}-Pad24)") (class "Default")
      (node (ref "U1") (pin "24") (pinfunction "~{DCD}_24") (pintype "passive+no_connect"))
    )
    (net (code "91") (name "unconnected-(U1-~{DSR}-Pad22)") (class "Default")
      (node (ref "U1") (pin "22") (pinfunction "~{DSR}_22") (pintype "passive+no_connect"))
    )
    (net (code "92") (name "unconnected-(U1-~{RI}{slash}CLK-Pad1)") (class "Default")
      (node (ref "U1") (pin "1") (pinfunction "~{RI}/CLK_1") (pintype "passive+no_connect"))
    )
    (net (code "93") (name "unconnected-(U1-~{SUSPEND}-Pad15)") (class "Default")
      (node (ref "U1") (pin "15") (pinfunction "~{SUSPEND}_15") (pintype "passive+no_connect"))
    )
  )
)
